# SCH_nrf-chip-pcb_2025-12-10.net
KiCad netlist of a schematic drawn in EasyEDA
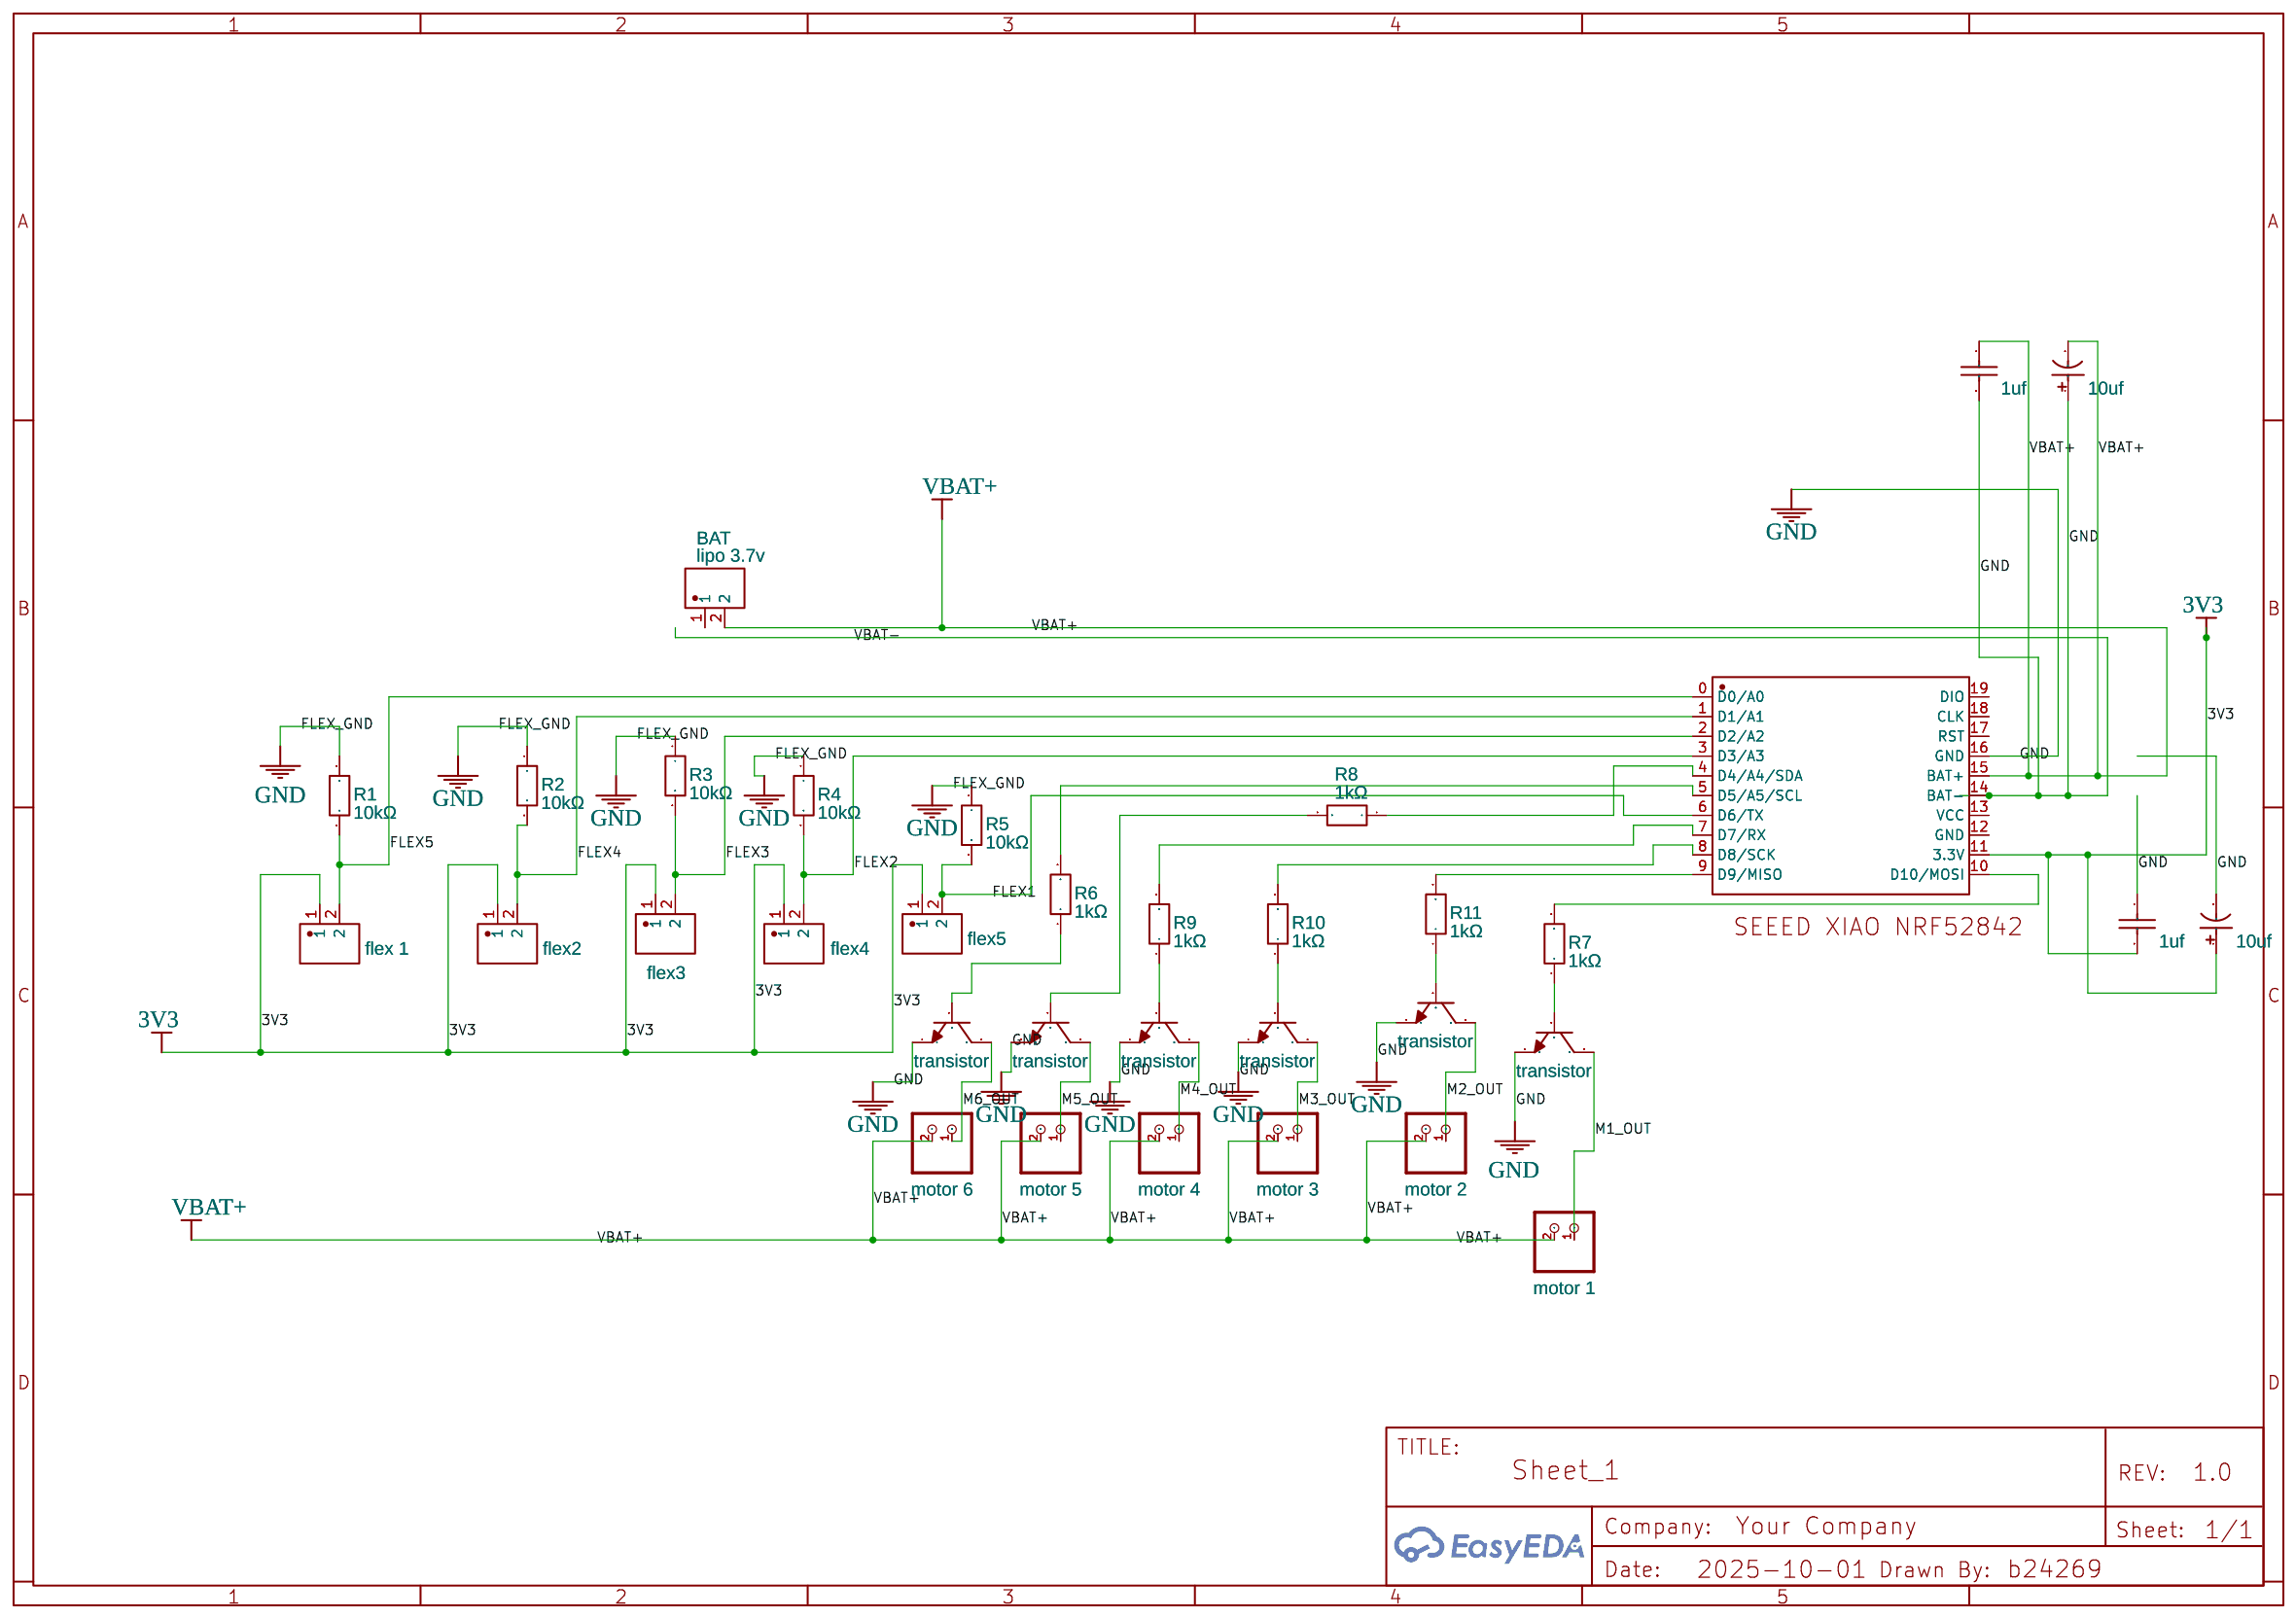
[diagram p0: schematic sheet]

(export (version "E")
  (design (tool "Eeschema 10.0.6"))
  (components
    (comp (ref "3V3CAP1") (value "1uf") (libsource (lib "") (part "Capacitor MLCC 0.1uF 25V 0603")))
    (comp (ref "3V3CAP10")
      (value "10uf")
      (fields (field (name "Manufacturer Part") "UVZ1E100MDD1TA") (field (name "Manufacturer") "Nichicon"))
      (libsource (lib "") (part "UVZ1E100MDD1TA_1"))
    )
    (comp (ref "BAT")
      (value "lipo 3.7v")
      (fields
        (field (name "Manufacturer Part") "2.0-2P ZZDK-R PCB Connector")
        (field (name "Manufacturer") "SHOU HAN(首韩)")
      )
      (libsource (lib "") (part "2.0-2P ZZDK-R PCB CONNECTOR"))
    )
    (comp (ref "BATCAP1") (value "1uf") (libsource (lib "") (part "Capacitor MLCC 0.1uF 25V 0603_1")))
    (comp (ref "BATCAP10")
      (value "10uf")
      (fields (field (name "Manufacturer Part") "UVZ1E100MDD1TA") (field (name "Manufacturer") "Nichicon"))
      (libsource (lib "") (part "UVZ1E100MDD1TA"))
    )
    (comp (ref "M1") (value "motor 1") (libsource (lib "") (part "JST_2PIN-THM")))
    (comp (ref "M2") (value "motor 2") (libsource (lib "") (part "JST_2PIN-THM")))
    (comp (ref "M3") (value "motor 3") (libsource (lib "") (part "JST_2PIN-THM")))
    (comp (ref "M4") (value "motor 4") (libsource (lib "") (part "JST_2PIN-THM")))
    (comp (ref "M5") (value "motor 5") (libsource (lib "") (part "JST_2PIN-THM")))
    (comp (ref "M6") (value "motor 6") (libsource (lib "") (part "JST_2PIN-THM")))
    (comp (ref "NRF") (value "SEEED XAIO NRF52840") (libsource (lib "") (part "SEEED XAIO NRF52840")))
    (comp (ref "Q1")
      (value "transistor")
      (fields (field (name "Manufacturer Part") "2n3904S-RTK/PS") (field (name "Manufacturer") "KEC"))
      (libsource (lib "") (part "2N3904(SOT-23)"))
    )
    (comp (ref "Q2")
      (value "transistor")
      (fields (field (name "Manufacturer Part") "2n3904S-RTK/PS") (field (name "Manufacturer") "KEC"))
      (libsource (lib "") (part "2N3904(SOT-23)"))
    )
    (comp (ref "Q3")
      (value "transistor")
      (fields (field (name "Manufacturer Part") "2n3904S-RTK/PS") (field (name "Manufacturer") "KEC"))
      (libsource (lib "") (part "2N3904(SOT-23)"))
    )
    (comp (ref "Q4")
      (value "transistor")
      (fields (field (name "Manufacturer Part") "2n3904S-RTK/PS") (field (name "Manufacturer") "KEC"))
      (libsource (lib "") (part "2N3904(SOT-23)"))
    )
    (comp (ref "Q5")
      (value "transistor")
      (fields (field (name "Manufacturer Part") "2n3904S-RTK/PS") (field (name "Manufacturer") "KEC"))
      (libsource (lib "") (part "2N3904(SOT-23)"))
    )
    (comp (ref "Q6")
      (value "transistor")
      (fields (field (name "Manufacturer Part") "2n3904S-RTK/PS") (field (name "Manufacturer") "KEC"))
      (libsource (lib "") (part "2N3904(SOT-23)"))
    )
    (comp (ref "R1")
      (value "10kΩ")
      (fields
        (field (name "Manufacturer Part") "TFCR0603-10W-C-1002FT")
        (field (name "Manufacturer") "Venkel")
      )
      (libsource (lib "") (part "TFCR0603-10W-C-1002FT"))
    )
    (comp (ref "R2")
      (value "10kΩ")
      (fields
        (field (name "Manufacturer Part") "TFCR0603-10W-C-1002FT")
        (field (name "Manufacturer") "Venkel")
      )
      (libsource (lib "") (part "TFCR0603-10W-C-1002FT"))
    )
    (comp (ref "R3")
      (value "10kΩ")
      (fields
        (field (name "Manufacturer Part") "TFCR0603-10W-C-1002FT")
        (field (name "Manufacturer") "Venkel")
      )
      (libsource (lib "") (part "TFCR0603-10W-C-1002FT"))
    )
    (comp (ref "R4")
      (value "10kΩ")
      (fields
        (field (name "Manufacturer Part") "TFCR0603-10W-C-1002FT")
        (field (name "Manufacturer") "Venkel")
      )
      (libsource (lib "") (part "TFCR0603-10W-C-1002FT"))
    )
    (comp (ref "R5")
      (value "10kΩ")
      (fields
        (field (name "Manufacturer Part") "TFCR0603-10W-C-1002FT")
        (field (name "Manufacturer") "Venkel")
      )
      (libsource (lib "") (part "TFCR0603-10W-C-1002FT"))
    )
    (comp (ref "R6")
      (value "1kΩ")
      (fields (field (name "Manufacturer Part") "PTFR0603Q1K00N9") (field (name "Manufacturer") "RESI(开步睿思)"))
      (libsource (lib "") (part "PTFR0603Q1K00N9"))
    )
    (comp (ref "R7")
      (value "1kΩ")
      (fields (field (name "Manufacturer Part") "PTFR0603Q1K00N9") (field (name "Manufacturer") "RESI(开步睿思)"))
      (libsource (lib "") (part "PTFR0603Q1K00N9"))
    )
    (comp (ref "R8")
      (value "1kΩ")
      (fields (field (name "Manufacturer Part") "PTFR0603Q1K00N9") (field (name "Manufacturer") "RESI(开步睿思)"))
      (libsource (lib "") (part "PTFR0603Q1K00N9_1"))
    )
    (comp (ref "R9")
      (value "1kΩ")
      (fields (field (name "Manufacturer Part") "PTFR0603Q1K00N9") (field (name "Manufacturer") "RESI(开步睿思)"))
      (libsource (lib "") (part "PTFR0603Q1K00N9"))
    )
    (comp (ref "R10")
      (value "1kΩ")
      (fields (field (name "Manufacturer Part") "PTFR0603Q1K00N9") (field (name "Manufacturer") "RESI(开步睿思)"))
      (libsource (lib "") (part "PTFR0603Q1K00N9"))
    )
    (comp (ref "R11")
      (value "1kΩ")
      (fields (field (name "Manufacturer Part") "PTFR0603Q1K00N9") (field (name "Manufacturer") "RESI(开步睿思)"))
      (libsource (lib "") (part "PTFR0603Q1K00N9"))
    )
    (comp (ref "U1")
      (value "flex5")
      (fields
        (field (name "Manufacturer Part") "5BML8-11732-102-W0")
        (field (name "Manufacturer") "SAMZO(三佐)")
      )
      (libsource (lib "") (part "5BML8-11732-102-W0"))
    )
    (comp (ref "U2")
      (value "flex 1")
      (fields
        (field (name "Manufacturer Part") "5BML8-11732-102-W0")
        (field (name "Manufacturer") "SAMZO(三佐)")
      )
      (libsource (lib "") (part "5BML8-11732-102-W0"))
    )
    (comp (ref "U3")
      (value "flex2")
      (fields
        (field (name "Manufacturer Part") "5BML8-11732-102-W0")
        (field (name "Manufacturer") "SAMZO(三佐)")
      )
      (libsource (lib "") (part "5BML8-11732-102-W0"))
    )
    (comp (ref "U4")
      (value "flex3")
      (fields
        (field (name "Manufacturer Part") "5BML8-11732-102-W0")
        (field (name "Manufacturer") "SAMZO(三佐)")
      )
      (libsource (lib "") (part "5BML8-11732-102-W0"))
    )
    (comp (ref "U5")
      (value "flex4")
      (fields
        (field (name "Manufacturer Part") "5BML8-11732-102-W0")
        (field (name "Manufacturer") "SAMZO(三佐)")
      )
      (libsource (lib "") (part "5BML8-11732-102-W0"))
    )
  )
  (nets
    (net (code "1") (name "/FLEX1") (class "Default")
      (node (ref "NRF") (pin "6") (pinfunction "D6/TX_6") (pintype "unspecified"))
      (node (ref "R5") (pin "2") (pinfunction "2_2") (pintype "unspecified"))
      (node (ref "U1") (pin "2") (pinfunction "2_2") (pintype "unspecified"))
    )
    (net (code "2") (name "/FLEX2") (class "Default")
      (node (ref "NRF") (pin "3") (pinfunction "D3/A3_3") (pintype "unspecified"))
      (node (ref "R4") (pin "2") (pinfunction "2_2") (pintype "unspecified"))
      (node (ref "U5") (pin "2") (pinfunction "2_2") (pintype "unspecified"))
    )
    (net (code "3") (name "/FLEX3") (class "Default")
      (node (ref "NRF") (pin "2") (pinfunction "D2/A2_2") (pintype "unspecified"))
      (node (ref "R3") (pin "2") (pinfunction "2_2") (pintype "unspecified"))
      (node (ref "U4") (pin "2") (pinfunction "2_2") (pintype "unspecified"))
    )
    (net (code "4") (name "/FLEX4") (class "Default")
      (node (ref "NRF") (pin "1") (pinfunction "D1/A1_1") (pintype "unspecified"))
      (node (ref "R2") (pin "2") (pinfunction "2_2") (pintype "unspecified"))
      (node (ref "U3") (pin "2") (pinfunction "2_2") (pintype "unspecified"))
    )
    (net (code "5") (name "/FLEX5") (class "Default")
      (node (ref "NRF") (pin "0") (pinfunction "D0/A0_0") (pintype "unspecified"))
      (node (ref "R1") (pin "2") (pinfunction "2_2") (pintype "unspecified"))
      (node (ref "U2") (pin "2") (pinfunction "2_2") (pintype "unspecified"))
    )
    (net (code "6") (name "/M1_OUT") (class "Default")
      (node (ref "M1") (pin "1") (pinfunction "2_1") (pintype "bidirectional"))
      (node (ref "Q1") (pin "3") (pinfunction "C_3") (pintype "input"))
    )
    (net (code "7") (name "/M2_OUT") (class "Default")
      (node (ref "M2") (pin "1") (pinfunction "2_1") (pintype "bidirectional"))
      (node (ref "Q2") (pin "3") (pinfunction "C_3") (pintype "input"))
    )
    (net (code "8") (name "/M3_OUT") (class "Default")
      (node (ref "M3") (pin "1") (pinfunction "2_1") (pintype "bidirectional"))
      (node (ref "Q3") (pin "3") (pinfunction "C_3") (pintype "input"))
    )
    (net (code "9") (name "/M4_OUT") (class "Default")
      (node (ref "M4") (pin "1") (pinfunction "2_1") (pintype "bidirectional"))
      (node (ref "Q4") (pin "3") (pinfunction "C_3") (pintype "input"))
    )
    (net (code "10") (name "/M5_OUT") (class "Default")
      (node (ref "M5") (pin "1") (pinfunction "2_1") (pintype "bidirectional"))
      (node (ref "Q5") (pin "3") (pinfunction "C_3") (pintype "input"))
    )
    (net (code "11") (name "/M6_OUT") (class "Default")
      (node (ref "M6") (pin "1") (pinfunction "2_1") (pintype "bidirectional"))
      (node (ref "Q6") (pin "3") (pinfunction "C_3") (pintype "input"))
    )
    (net (code "12") (name "3V3") (class "Default")
      (node (ref "3V3CAP1") (pin "2") (pinfunction "2_2") (pintype "unspecified"))
      (node (ref "3V3CAP10") (pin "1") (pinfunction "1_1") (pintype "input"))
      (node (ref "NRF") (pin "11") (pinfunction "3.3V_11") (pintype "unspecified"))
      (node (ref "U1") (pin "1") (pinfunction "1_1") (pintype "unspecified"))
      (node (ref "U2") (pin "1") (pinfunction "1_1") (pintype "unspecified"))
      (node (ref "U3") (pin "1") (pinfunction "1_1") (pintype "unspecified"))
      (node (ref "U4") (pin "1") (pinfunction "1_1") (pintype "unspecified"))
      (node (ref "U5") (pin "1") (pinfunction "1_1") (pintype "unspecified"))
    )
    (net (code "13") (name "GND") (class "Default")
      (node (ref "3V3CAP1") (pin "1") (pinfunction "1_1") (pintype "unspecified"))
      (node (ref "3V3CAP10") (pin "2") (pinfunction "2_2") (pintype "input"))
      (node (ref "BATCAP1") (pin "2") (pinfunction "2_2") (pintype "unspecified"))
      (node (ref "BATCAP10") (pin "1") (pinfunction "1_1") (pintype "input"))
      (node (ref "NRF") (pin "14") (pinfunction "BAT-_14") (pintype "unspecified"))
      (node (ref "NRF") (pin "16") (pinfunction "GND_16") (pintype "unspecified"))
      (node (ref "Q1") (pin "1") (pinfunction "E_1") (pintype "input"))
      (node (ref "Q2") (pin "1") (pinfunction "E_1") (pintype "input"))
      (node (ref "Q3") (pin "1") (pinfunction "E_1") (pintype "input"))
      (node (ref "Q4") (pin "1") (pinfunction "E_1") (pintype "input"))
      (node (ref "Q5") (pin "1") (pinfunction "E_1") (pintype "input"))
      (node (ref "Q6") (pin "1") (pinfunction "E_1") (pintype "input"))
      (node (ref "R1") (pin "1") (pinfunction "1_1") (pintype "unspecified"))
      (node (ref "R2") (pin "1") (pinfunction "1_1") (pintype "unspecified"))
      (node (ref "R3") (pin "1") (pinfunction "1_1") (pintype "unspecified"))
      (node (ref "R4") (pin "1") (pinfunction "1_1") (pintype "unspecified"))
      (node (ref "R5") (pin "1") (pinfunction "1_1") (pintype "unspecified"))
    )
    (net (code "14") (name "Net-(NRF-D4{slash}A4{slash}SDA)") (class "Default")
      (node (ref "NRF") (pin "4") (pinfunction "D4/A4/SDA_4") (pintype "unspecified"))
      (node (ref "R8") (pin "1") (pinfunction "1_1") (pintype "unspecified"))
    )
    (net (code "15") (name "Net-(NRF-D5{slash}A5{slash}SCL)") (class "Default")
      (node (ref "NRF") (pin "5") (pinfunction "D5/A5/SCL_5") (pintype "unspecified"))
      (node (ref "R6") (pin "2") (pinfunction "2_2") (pintype "unspecified"))
    )
    (net (code "16") (name "Net-(NRF-D7{slash}RX)") (class "Default")
      (node (ref "NRF") (pin "7") (pinfunction "D7/RX_7") (pintype "unspecified"))
      (node (ref "R9") (pin "2") (pinfunction "2_2") (pintype "unspecified"))
    )
    (net (code "17") (name "Net-(NRF-D8{slash}SCK)") (class "Default")
      (node (ref "NRF") (pin "8") (pinfunction "D8/SCK_8") (pintype "unspecified"))
      (node (ref "R10") (pin "2") (pinfunction "2_2") (pintype "unspecified"))
    )
    (net (code "18") (name "Net-(NRF-D9{slash}MISO)") (class "Default")
      (node (ref "NRF") (pin "9") (pinfunction "D9/MISO_9") (pintype "unspecified"))
      (node (ref "R11") (pin "2") (pinfunction "2_2") (pintype "unspecified"))
    )
    (net (code "19") (name "Net-(NRF-D10{slash}MOSI)") (class "Default")
      (node (ref "NRF") (pin "10") (pinfunction "D10/MOSI_10") (pintype "unspecified"))
      (node (ref "R7") (pin "2") (pinfunction "2_2") (pintype "unspecified"))
    )
    (net (code "20") (name "Net-(Q1-B)") (class "Default")
      (node (ref "Q1") (pin "2") (pinfunction "B_2") (pintype "input"))
      (node (ref "R7") (pin "1") (pinfunction "1_1") (pintype "unspecified"))
    )
    (net (code "21") (name "Net-(Q2-B)") (class "Default")
      (node (ref "Q2") (pin "2") (pinfunction "B_2") (pintype "input"))
      (node (ref "R11") (pin "1") (pinfunction "1_1") (pintype "unspecified"))
    )
    (net (code "22") (name "Net-(Q3-B)") (class "Default")
      (node (ref "Q3") (pin "2") (pinfunction "B_2") (pintype "input"))
      (node (ref "R10") (pin "1") (pinfunction "1_1") (pintype "unspecified"))
    )
    (net (code "23") (name "Net-(Q4-B)") (class "Default")
      (node (ref "Q4") (pin "2") (pinfunction "B_2") (pintype "input"))
      (node (ref "R9") (pin "1") (pinfunction "1_1") (pintype "unspecified"))
    )
    (net (code "24") (name "Net-(Q5-B)") (class "Default")
      (node (ref "Q5") (pin "2") (pinfunction "B_2") (pintype "input"))
      (node (ref "R8") (pin "2") (pinfunction "2_2") (pintype "unspecified"))
    )
    (net (code "25") (name "Net-(Q6-B)") (class "Default")
      (node (ref "Q6") (pin "2") (pinfunction "B_2") (pintype "input"))
      (node (ref "R6") (pin "1") (pinfunction "1_1") (pintype "unspecified"))
    )
    (net (code "26") (name "VBAT+") (class "Default")
      (node (ref "BAT") (pin "2") (pinfunction "2_2") (pintype "unspecified"))
      (node (ref "BATCAP1") (pin "1") (pinfunction "1_1") (pintype "unspecified"))
      (node (ref "BATCAP10") (pin "2") (pinfunction "2_2") (pintype "input"))
      (node (ref "M1") (pin "2") (pinfunction "1_2") (pintype "bidirectional"))
      (node (ref "M2") (pin "2") (pinfunction "1_2") (pintype "bidirectional"))
      (node (ref "M3") (pin "2") (pinfunction "1_2") (pintype "bidirectional"))
      (node (ref "M4") (pin "2") (pinfunction "1_2") (pintype "bidirectional"))
      (node (ref "M5") (pin "2") (pinfunction "1_2") (pintype "bidirectional"))
      (node (ref "M6") (pin "2") (pinfunction "1_2") (pintype "bidirectional"))
      (node (ref "NRF") (pin "15") (pinfunction "BAT+_15") (pintype "unspecified"))
    )
    (net (code "27") (name "unconnected-(BAT-Pad1)") (class "Default")
      (node (ref "BAT") (pin "1") (pinfunction "1_1") (pintype "unspecified"))
    )
    (net (code "28") (name "unconnected-(NRF-CLK-Pad18)") (class "Default")
      (node (ref "NRF") (pin "18") (pinfunction "CLK_18") (pintype "unspecified"))
    )
    (net (code "29") (name "unconnected-(NRF-DIO-Pad19)") (class "Default")
      (node (ref "NRF") (pin "19") (pinfunction "DIO_19") (pintype "unspecified"))
    )
    (net (code "30") (name "unconnected-(NRF-GND-Pad12)") (class "Default")
      (node (ref "NRF") (pin "12") (pinfunction "GND_12") (pintype "unspecified"))
    )
    (net (code "31") (name "unconnected-(NRF-RST-Pad17)") (class "Default")
      (node (ref "NRF") (pin "17") (pinfunction "RST_17") (pintype "unspecified"))
    )
    (net (code "32") (name "unconnected-(NRF-VCC-Pad13)") (class "Default")
      (node (ref "NRF") (pin "13") (pinfunction "VCC_13") (pintype "unspecified"))
    )
  )
)
